# interfacing.net
KiCad netlist of a schematic drawn in EAGLE
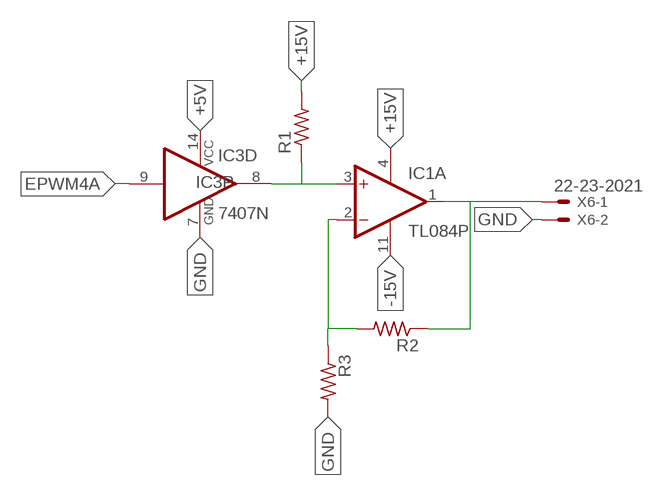
[diagram p0: schematic, sheet 1]

(export (version "E")
  (design (tool "Eeschema 10.0.6"))
  (components
    (comp (ref "IC1")
      (value "TL084P")
      (footprint "eagle-import:DIL14")
      (libsource (lib "eagle-import") (part "TL084P"))
    )
    (comp (ref "IC3")
      (value "7407N")
      (footprint "eagle-import:DIL14")
      (libsource (lib "eagle-import") (part "7407N"))
    )
    (comp (ref "R1")
      (value "R-US_0207/10")
      (footprint "eagle-import:0207_10")
      (libsource (lib "eagle-import") (part "R-US_0207/10"))
    )
    (comp (ref "R2")
      (value "R-US_0207/10")
      (footprint "eagle-import:0207_10")
      (libsource (lib "eagle-import") (part "R-US_0207/10"))
    )
    (comp (ref "R3")
      (value "R-US_0207/10")
      (footprint "eagle-import:0207_10")
      (libsource (lib "eagle-import") (part "R-US_0207/10"))
    )
    (comp (ref "X6")
      (value "22-23-2021")
      (footprint "eagle-import:22-23-2021")
      (fields (field (name "MF") "MOLEX"))
      (libsource (lib "eagle-import") (part "22-23-2021"))
    )
  )
  (nets
    (net (code "1") (name "+5V") (class "Default")
      (node (ref "IC3") (pin "14") (pinfunction "VCC_14") (pintype "power_in"))
    )
    (net (code "2") (name "+15V") (class "Default")
      (node (ref "IC1") (pin "4") (pinfunction "V+_4") (pintype "power_in"))
      (node (ref "R1") (pin "2") (pinfunction "2_2") (pintype "passive"))
    )
    (net (code "3") (name "-15V") (class "Default")
      (node (ref "IC1") (pin "11") (pinfunction "V-_11") (pintype "power_in"))
    )
    (net (code "4") (name "EPWM4A") (class "Default")
      (node (ref "IC3") (pin "9") (pinfunction "I_9") (pintype "input"))
    )
    (net (code "5") (name "GND") (class "Default")
      (node (ref "IC3") (pin "7") (pinfunction "GND_7") (pintype "power_in"))
      (node (ref "R3") (pin "2") (pinfunction "2_2") (pintype "passive"))
      (node (ref "X6") (pin "2") (pinfunction "S_2") (pintype "passive"))
    )
    (net (code "6") (name "Net-(IC1A-+IN)") (class "Default")
      (node (ref "IC1") (pin "3") (pinfunction "+IN_3") (pintype "input"))
      (node (ref "IC3") (pin "8") (pinfunction "O_8") (pintype "open_collector"))
      (node (ref "R1") (pin "1") (pinfunction "1_1") (pintype "passive"))
    )
    (net (code "7") (name "Net-(IC1A--IN)") (class "Default")
      (node (ref "IC1") (pin "2") (pinfunction "-IN_2") (pintype "input"))
      (node (ref "R2") (pin "2") (pinfunction "2_2") (pintype "passive"))
      (node (ref "R3") (pin "1") (pinfunction "1_1") (pintype "passive"))
    )
    (net (code "8") (name "Net-(IC1A-OUT)") (class "Default")
      (node (ref "IC1") (pin "1") (pinfunction "OUT_1") (pintype "output"))
      (node (ref "R2") (pin "1") (pinfunction "1_1") (pintype "passive"))
      (node (ref "X6") (pin "1") (pinfunction "S_1") (pintype "passive"))
    )
  )
)
